# shield-iblock.net
KiCad netlist of a schematic drawn in EAGLE
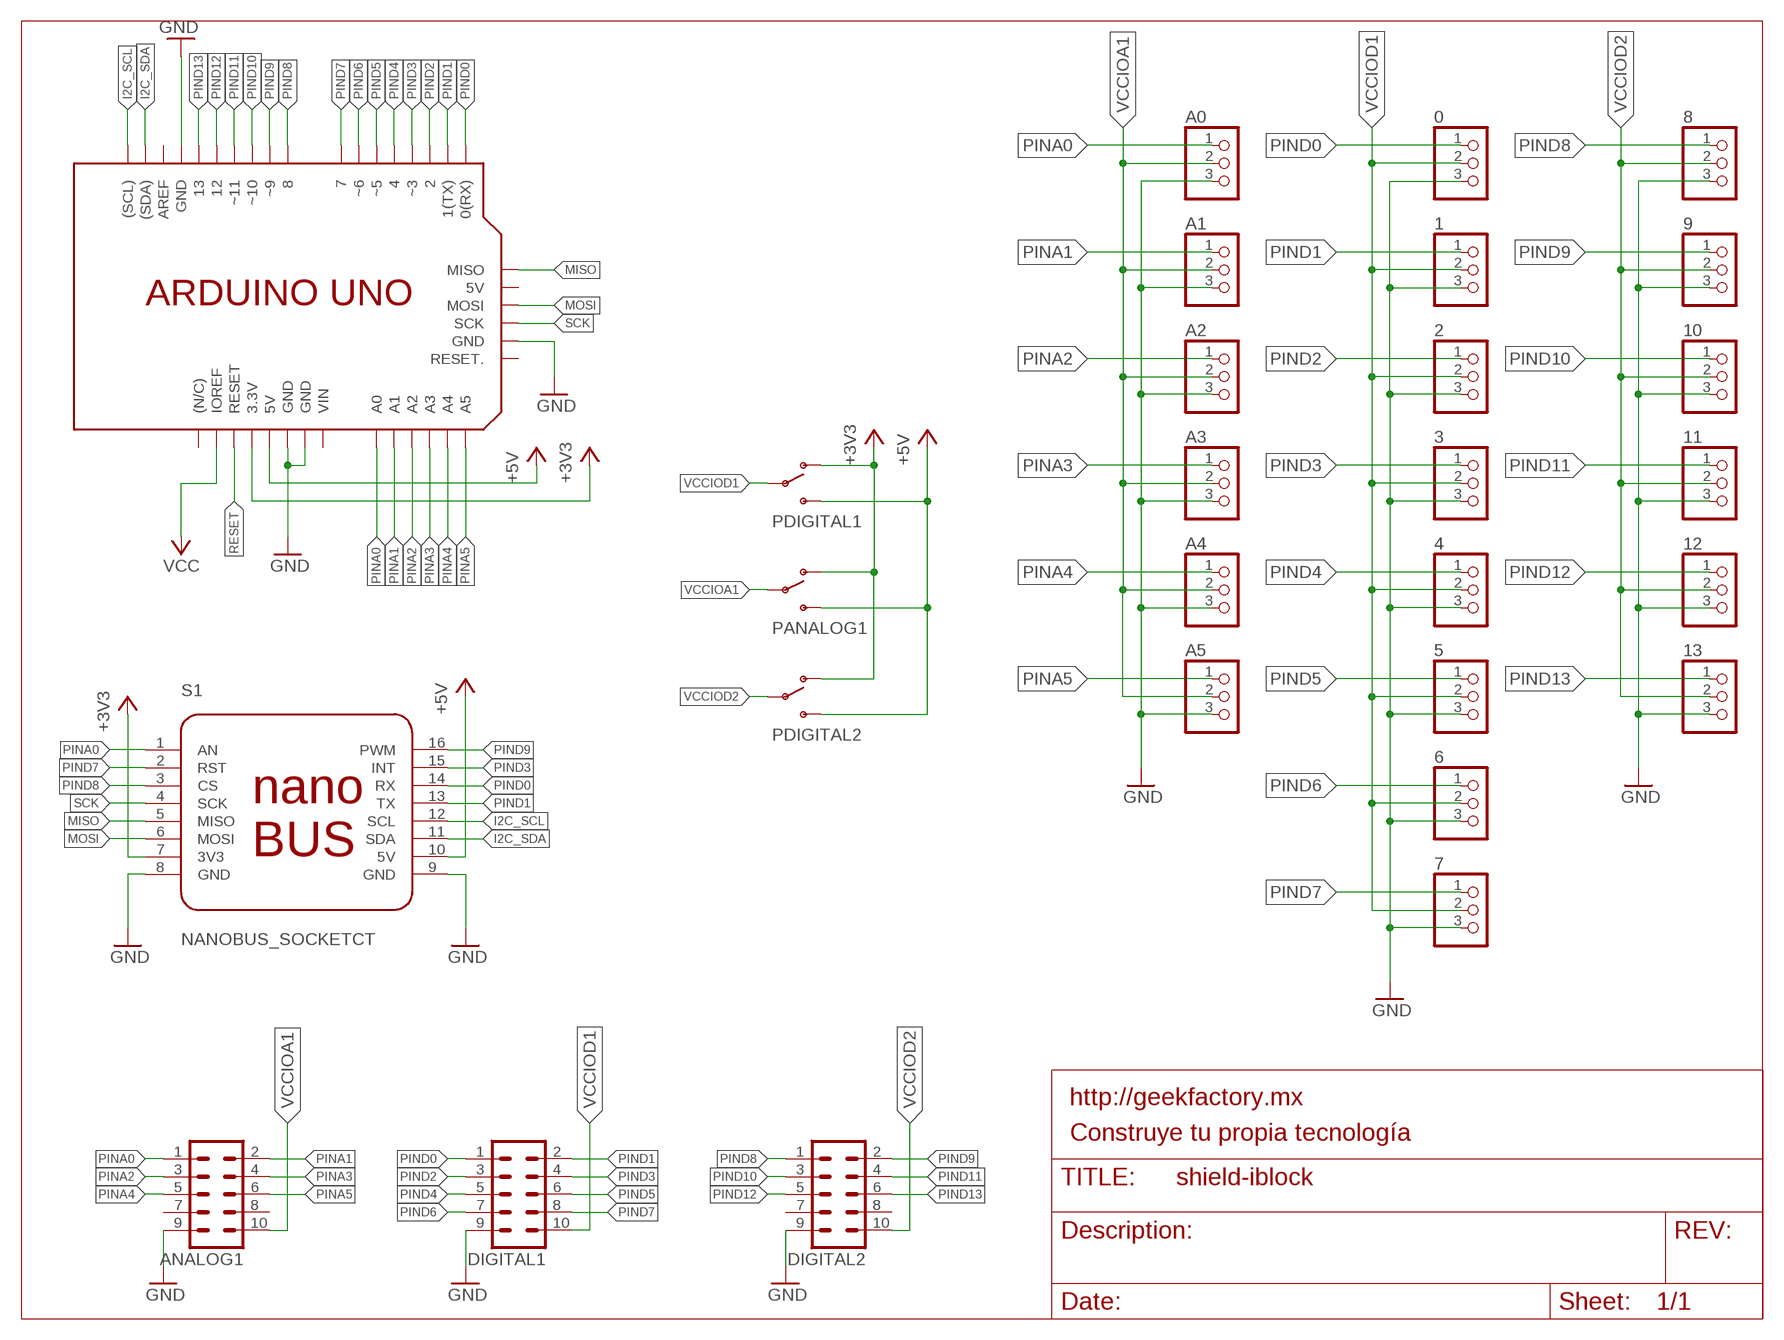
[diagram p0: schematic, sheet 1]

(export (version "E")
  (design (tool "Eeschema 10.0.6"))
  (components
    (comp (ref "0")
      (value "PINHD-1X3")
      (footprint "eagle-import:1X03")
      (libsource (lib "eagle-import") (part "PINHD-1X3"))
    )
    (comp (ref "1")
      (value "PINHD-1X3")
      (footprint "eagle-import:1X03")
      (libsource (lib "eagle-import") (part "PINHD-1X3"))
    )
    (comp (ref "2")
      (value "PINHD-1X3")
      (footprint "eagle-import:1X03")
      (libsource (lib "eagle-import") (part "PINHD-1X3"))
    )
    (comp (ref "3")
      (value "PINHD-1X3")
      (footprint "eagle-import:1X03")
      (libsource (lib "eagle-import") (part "PINHD-1X3"))
    )
    (comp (ref "4")
      (value "PINHD-1X3")
      (footprint "eagle-import:1X03")
      (libsource (lib "eagle-import") (part "PINHD-1X3"))
    )
    (comp (ref "5")
      (value "PINHD-1X3")
      (footprint "eagle-import:1X03")
      (libsource (lib "eagle-import") (part "PINHD-1X3"))
    )
    (comp (ref "6")
      (value "PINHD-1X3")
      (footprint "eagle-import:1X03")
      (libsource (lib "eagle-import") (part "PINHD-1X3"))
    )
    (comp (ref "7")
      (value "PINHD-1X3")
      (footprint "eagle-import:1X03")
      (libsource (lib "eagle-import") (part "PINHD-1X3"))
    )
    (comp (ref "8")
      (value "PINHD-1X3")
      (footprint "eagle-import:1X03")
      (libsource (lib "eagle-import") (part "PINHD-1X3"))
    )
    (comp (ref "9")
      (value "PINHD-1X3")
      (footprint "eagle-import:1X03")
      (libsource (lib "eagle-import") (part "PINHD-1X3"))
    )
    (comp (ref "10")
      (value "PINHD-1X3")
      (footprint "eagle-import:1X03")
      (libsource (lib "eagle-import") (part "PINHD-1X3"))
    )
    (comp (ref "11")
      (value "PINHD-1X3")
      (footprint "eagle-import:1X03")
      (libsource (lib "eagle-import") (part "PINHD-1X3"))
    )
    (comp (ref "12")
      (value "PINHD-1X3")
      (footprint "eagle-import:1X03")
      (libsource (lib "eagle-import") (part "PINHD-1X3"))
    )
    (comp (ref "13")
      (value "PINHD-1X3")
      (footprint "eagle-import:1X03")
      (libsource (lib "eagle-import") (part "PINHD-1X3"))
    )
    (comp (ref "A0")
      (value "PINHD-1X3")
      (footprint "eagle-import:1X03")
      (libsource (lib "eagle-import") (part "PINHD-1X3"))
    )
    (comp (ref "A1")
      (value "PINHD-1X3")
      (footprint "eagle-import:1X03")
      (libsource (lib "eagle-import") (part "PINHD-1X3"))
    )
    (comp (ref "A2")
      (value "PINHD-1X3")
      (footprint "eagle-import:1X03")
      (libsource (lib "eagle-import") (part "PINHD-1X3"))
    )
    (comp (ref "A3")
      (value "PINHD-1X3")
      (footprint "eagle-import:1X03")
      (libsource (lib "eagle-import") (part "PINHD-1X3"))
    )
    (comp (ref "A4")
      (value "PINHD-1X3")
      (footprint "eagle-import:1X03")
      (libsource (lib "eagle-import") (part "PINHD-1X3"))
    )
    (comp (ref "A5")
      (value "PINHD-1X3")
      (footprint "eagle-import:1X03")
      (libsource (lib "eagle-import") (part "PINHD-1X3"))
    )
    (comp (ref "ANALOG1")
      (value "MA05-2A")
      (footprint "eagle-import:MA05-2A")
      (libsource (lib "eagle-import") (part "MA05-2A"))
    )
    (comp (ref "ARDUINO1")
      (value "ARDUINO_UNO_NHNBR")
      (footprint "eagle-import:ARDUINO_UNO_NH_NB_ROUND")
      (libsource (lib "eagle-import") (part "ARDUINO_UNO_NHNBR"))
    )
    (comp (ref "DIGITAL1")
      (value "MA05-2A")
      (footprint "eagle-import:MA05-2A")
      (libsource (lib "eagle-import") (part "MA05-2A"))
    )
    (comp (ref "DIGITAL2")
      (value "MA05-2A")
      (footprint "eagle-import:MA05-2A")
      (libsource (lib "eagle-import") (part "MA05-2A"))
    )
    (comp (ref "PANALOG1")
      (value "SWITCH-SPSTPTH")
      (footprint "eagle-import:SWITCH-SPDT")
      (libsource (lib "eagle-import") (part "SWITCH-SPSTPTH"))
    )
    (comp (ref "PDIGITAL1")
      (value "SWITCH-SPSTPTH")
      (footprint "eagle-import:SWITCH-SPDT")
      (libsource (lib "eagle-import") (part "SWITCH-SPSTPTH"))
    )
    (comp (ref "PDIGITAL2")
      (value "SWITCH-SPSTPTH")
      (footprint "eagle-import:SWITCH-SPDT")
      (libsource (lib "eagle-import") (part "SWITCH-SPSTPTH"))
    )
    (comp (ref "S1")
      (value "NANOBUS_SOCKETCT")
      (footprint "eagle-import:NANOBUS_CONNECTOR_CLEAR_TOP")
      (libsource (lib "eagle-import") (part "NANOBUS_SOCKETCT"))
    )
  )
  (nets
    (net (code "1") (name "+3V3") (class "Default")
      (node (ref "ARDUINO1") (pin "3V3") (pinfunction "3.3V_3V3") (pintype "bidirectional"))
      (node (ref "PANALOG1") (pin "1") (pinfunction "O_1") (pintype "passive"))
      (node (ref "PDIGITAL1") (pin "1") (pinfunction "O_1") (pintype "passive"))
      (node (ref "PDIGITAL2") (pin "1") (pinfunction "O_1") (pintype "passive"))
      (node (ref "S1") (pin "7") (pinfunction "3V3_7") (pintype "power_in"))
    )
    (net (code "2") (name "+5V") (class "Default")
      (node (ref "ARDUINO1") (pin "5V") (pinfunction "5V_5V") (pintype "bidirectional"))
      (node (ref "PANALOG1") (pin "3") (pinfunction "S_3") (pintype "passive"))
      (node (ref "PDIGITAL1") (pin "3") (pinfunction "S_3") (pintype "passive"))
      (node (ref "PDIGITAL2") (pin "3") (pinfunction "S_3") (pintype "passive"))
      (node (ref "S1") (pin "10") (pinfunction "5V_10") (pintype "power_in"))
    )
    (net (code "3") (name "GND") (class "Default")
      (node (ref "0") (pin "3") (pinfunction "3_3") (pintype "passive"))
      (node (ref "1") (pin "3") (pinfunction "3_3") (pintype "passive"))
      (node (ref "10") (pin "3") (pinfunction "3_3") (pintype "passive"))
      (node (ref "11") (pin "3") (pinfunction "3_3") (pintype "passive"))
      (node (ref "12") (pin "3") (pinfunction "3_3") (pintype "passive"))
      (node (ref "13") (pin "3") (pinfunction "3_3") (pintype "passive"))
      (node (ref "2") (pin "3") (pinfunction "3_3") (pintype "passive"))
      (node (ref "3") (pin "3") (pinfunction "3_3") (pintype "passive"))
      (node (ref "4") (pin "3") (pinfunction "3_3") (pintype "passive"))
      (node (ref "5") (pin "3") (pinfunction "3_3") (pintype "passive"))
      (node (ref "6") (pin "3") (pinfunction "3_3") (pintype "passive"))
      (node (ref "7") (pin "3") (pinfunction "3_3") (pintype "passive"))
      (node (ref "8") (pin "3") (pinfunction "3_3") (pintype "passive"))
      (node (ref "9") (pin "3") (pinfunction "3_3") (pintype "passive"))
      (node (ref "A0") (pin "3") (pinfunction "3_3") (pintype "passive"))
      (node (ref "A1") (pin "3") (pinfunction "3_3") (pintype "passive"))
      (node (ref "A2") (pin "3") (pinfunction "3_3") (pintype "passive"))
      (node (ref "A3") (pin "3") (pinfunction "3_3") (pintype "passive"))
      (node (ref "A4") (pin "3") (pinfunction "3_3") (pintype "passive"))
      (node (ref "A5") (pin "3") (pinfunction "3_3") (pintype "passive"))
      (node (ref "ANALOG1") (pin "9") (pinfunction "9_9") (pintype "passive"))
      (node (ref "ARDUINO1") (pin "GND") (pinfunction "GND_GND") (pintype "bidirectional"))
      (node (ref "ARDUINO1") (pin "GND.") (pinfunction "GND_GND.") (pintype "bidirectional"))
      (node (ref "ARDUINO1") (pin "GND..") (pinfunction "GND_GND..") (pintype "bidirectional"))
      (node (ref "ARDUINO1") (pin "GND_") (pinfunction "GND_GND_") (pintype "bidirectional"))
      (node (ref "DIGITAL1") (pin "9") (pinfunction "9_9") (pintype "passive"))
      (node (ref "DIGITAL2") (pin "9") (pinfunction "9_9") (pintype "passive"))
      (node (ref "S1") (pin "8") (pinfunction "GND_8") (pintype "power_in"))
      (node (ref "S1") (pin "9") (pinfunction "GND_9") (pintype "power_in"))
    )
    (net (code "4") (name "I2C_SCL") (class "Default")
      (node (ref "ARDUINO1") (pin "SCL") (pinfunction "(SCL)_SCL") (pintype "bidirectional"))
      (node (ref "S1") (pin "12") (pinfunction "SCL_12") (pintype "passive"))
    )
    (net (code "5") (name "I2C_SDA") (class "Default")
      (node (ref "ARDUINO1") (pin "SDA") (pinfunction "(SDA)_SDA") (pintype "bidirectional"))
      (node (ref "S1") (pin "11") (pinfunction "SDA_11") (pintype "passive"))
    )
    (net (code "6") (name "MISO") (class "Default")
      (node (ref "ARDUINO1") (pin "MISO") (pinfunction "MISO_MISO") (pintype "bidirectional"))
      (node (ref "S1") (pin "5") (pinfunction "MISO_5") (pintype "passive"))
    )
    (net (code "7") (name "MOSI") (class "Default")
      (node (ref "ARDUINO1") (pin "MOSI") (pinfunction "MOSI_MOSI") (pintype "bidirectional"))
      (node (ref "S1") (pin "6") (pinfunction "MOSI_6") (pintype "passive"))
    )
    (net (code "8") (name "PINA0") (class "Default")
      (node (ref "A0") (pin "1") (pinfunction "1_1") (pintype "passive"))
      (node (ref "ANALOG1") (pin "1") (pinfunction "1_1") (pintype "passive"))
      (node (ref "ARDUINO1") (pin "A0") (pinfunction "A0_A0") (pintype "bidirectional"))
      (node (ref "S1") (pin "1") (pinfunction "AN_1") (pintype "passive"))
    )
    (net (code "9") (name "PINA1") (class "Default")
      (node (ref "A1") (pin "1") (pinfunction "1_1") (pintype "passive"))
      (node (ref "ANALOG1") (pin "2") (pinfunction "2_2") (pintype "passive"))
      (node (ref "ARDUINO1") (pin "A1") (pinfunction "A1_A1") (pintype "bidirectional"))
    )
    (net (code "10") (name "PINA2") (class "Default")
      (node (ref "A2") (pin "1") (pinfunction "1_1") (pintype "passive"))
      (node (ref "ANALOG1") (pin "3") (pinfunction "3_3") (pintype "passive"))
      (node (ref "ARDUINO1") (pin "A2") (pinfunction "A2_A2") (pintype "bidirectional"))
    )
    (net (code "11") (name "PINA3") (class "Default")
      (node (ref "A3") (pin "1") (pinfunction "1_1") (pintype "passive"))
      (node (ref "ANALOG1") (pin "4") (pinfunction "4_4") (pintype "passive"))
      (node (ref "ARDUINO1") (pin "A3") (pinfunction "A3_A3") (pintype "bidirectional"))
    )
    (net (code "12") (name "PINA4") (class "Default")
      (node (ref "A4") (pin "1") (pinfunction "1_1") (pintype "passive"))
      (node (ref "ANALOG1") (pin "5") (pinfunction "5_5") (pintype "passive"))
      (node (ref "ARDUINO1") (pin "A4") (pinfunction "A4_A4") (pintype "bidirectional"))
    )
    (net (code "13") (name "PINA5") (class "Default")
      (node (ref "A5") (pin "1") (pinfunction "1_1") (pintype "passive"))
      (node (ref "ANALOG1") (pin "6") (pinfunction "6_6") (pintype "passive"))
      (node (ref "ARDUINO1") (pin "A5") (pinfunction "A5_A5") (pintype "bidirectional"))
    )
    (net (code "14") (name "PIND0") (class "Default")
      (node (ref "0") (pin "1") (pinfunction "1_1") (pintype "passive"))
      (node (ref "ARDUINO1") (pin "0") (pinfunction "0(RX)_0") (pintype "bidirectional"))
      (node (ref "DIGITAL1") (pin "1") (pinfunction "1_1") (pintype "passive"))
      (node (ref "S1") (pin "14") (pinfunction "RX_14") (pintype "passive"))
    )
    (net (code "15") (name "PIND1") (class "Default")
      (node (ref "1") (pin "1") (pinfunction "1_1") (pintype "passive"))
      (node (ref "ARDUINO1") (pin "1") (pinfunction "1(TX)_1") (pintype "bidirectional"))
      (node (ref "DIGITAL1") (pin "2") (pinfunction "2_2") (pintype "passive"))
      (node (ref "S1") (pin "13") (pinfunction "TX_13") (pintype "passive"))
    )
    (net (code "16") (name "PIND2") (class "Default")
      (node (ref "2") (pin "1") (pinfunction "1_1") (pintype "passive"))
      (node (ref "ARDUINO1") (pin "2") (pinfunction "2_2") (pintype "bidirectional"))
      (node (ref "DIGITAL1") (pin "3") (pinfunction "3_3") (pintype "passive"))
    )
    (net (code "17") (name "PIND3") (class "Default")
      (node (ref "3") (pin "1") (pinfunction "1_1") (pintype "passive"))
      (node (ref "ARDUINO1") (pin "3") (pinfunction "~{3}_3") (pintype "bidirectional"))
      (node (ref "DIGITAL1") (pin "4") (pinfunction "4_4") (pintype "passive"))
      (node (ref "S1") (pin "15") (pinfunction "INT_15") (pintype "passive"))
    )
    (net (code "18") (name "PIND4") (class "Default")
      (node (ref "4") (pin "1") (pinfunction "1_1") (pintype "passive"))
      (node (ref "ARDUINO1") (pin "4") (pinfunction "4_4") (pintype "bidirectional"))
      (node (ref "DIGITAL1") (pin "5") (pinfunction "5_5") (pintype "passive"))
    )
    (net (code "19") (name "PIND5") (class "Default")
      (node (ref "5") (pin "1") (pinfunction "1_1") (pintype "passive"))
      (node (ref "ARDUINO1") (pin "5") (pinfunction "~{5}_5") (pintype "bidirectional"))
      (node (ref "DIGITAL1") (pin "6") (pinfunction "6_6") (pintype "passive"))
    )
    (net (code "20") (name "PIND6") (class "Default")
      (node (ref "6") (pin "1") (pinfunction "1_1") (pintype "passive"))
      (node (ref "ARDUINO1") (pin "6") (pinfunction "~{6}_6") (pintype "bidirectional"))
      (node (ref "DIGITAL1") (pin "7") (pinfunction "7_7") (pintype "passive"))
    )
    (net (code "21") (name "PIND7") (class "Default")
      (node (ref "7") (pin "1") (pinfunction "1_1") (pintype "passive"))
      (node (ref "ARDUINO1") (pin "7") (pinfunction "7_7") (pintype "bidirectional"))
      (node (ref "DIGITAL1") (pin "8") (pinfunction "8_8") (pintype "passive"))
      (node (ref "S1") (pin "2") (pinfunction "RST_2") (pintype "passive"))
    )
    (net (code "22") (name "PIND8") (class "Default")
      (node (ref "8") (pin "1") (pinfunction "1_1") (pintype "passive"))
      (node (ref "ARDUINO1") (pin "8") (pinfunction "8_8") (pintype "bidirectional"))
      (node (ref "DIGITAL2") (pin "1") (pinfunction "1_1") (pintype "passive"))
      (node (ref "S1") (pin "3") (pinfunction "CS_3") (pintype "passive"))
    )
    (net (code "23") (name "PIND9") (class "Default")
      (node (ref "9") (pin "1") (pinfunction "1_1") (pintype "passive"))
      (node (ref "ARDUINO1") (pin "9") (pinfunction "~{9}_9") (pintype "bidirectional"))
      (node (ref "DIGITAL2") (pin "2") (pinfunction "2_2") (pintype "passive"))
      (node (ref "S1") (pin "16") (pinfunction "PWM_16") (pintype "passive"))
    )
    (net (code "24") (name "PIND10") (class "Default")
      (node (ref "10") (pin "1") (pinfunction "1_1") (pintype "passive"))
      (node (ref "ARDUINO1") (pin "10") (pinfunction "~{10}_10") (pintype "bidirectional"))
      (node (ref "DIGITAL2") (pin "3") (pinfunction "3_3") (pintype "passive"))
    )
    (net (code "25") (name "PIND11") (class "Default")
      (node (ref "11") (pin "1") (pinfunction "1_1") (pintype "passive"))
      (node (ref "ARDUINO1") (pin "11") (pinfunction "~{11}_11") (pintype "bidirectional"))
      (node (ref "DIGITAL2") (pin "4") (pinfunction "4_4") (pintype "passive"))
    )
    (net (code "26") (name "PIND12") (class "Default")
      (node (ref "12") (pin "1") (pinfunction "1_1") (pintype "passive"))
      (node (ref "ARDUINO1") (pin "12") (pinfunction "12_12") (pintype "bidirectional"))
      (node (ref "DIGITAL2") (pin "5") (pinfunction "5_5") (pintype "passive"))
    )
    (net (code "27") (name "PIND13") (class "Default")
      (node (ref "13") (pin "1") (pinfunction "1_1") (pintype "passive"))
      (node (ref "ARDUINO1") (pin "13") (pinfunction "13_13") (pintype "bidirectional"))
      (node (ref "DIGITAL2") (pin "6") (pinfunction "6_6") (pintype "passive"))
    )
    (net (code "28") (name "RESET") (class "Default")
      (node (ref "ARDUINO1") (pin "RST") (pinfunction "RESET_RST") (pintype "bidirectional"))
    )
    (net (code "29") (name "SCK") (class "Default")
      (node (ref "ARDUINO1") (pin "SCK") (pinfunction "SCK_SCK") (pintype "bidirectional"))
      (node (ref "S1") (pin "4") (pinfunction "SCK_4") (pintype "passive"))
    )
    (net (code "30") (name "VCC") (class "Default")
      (node (ref "ARDUINO1") (pin "IOR") (pinfunction "IOREF_IOR") (pintype "bidirectional"))
    )
    (net (code "31") (name "VCCIOA1") (class "Default")
      (node (ref "A0") (pin "2") (pinfunction "2_2") (pintype "passive"))
      (node (ref "A1") (pin "2") (pinfunction "2_2") (pintype "passive"))
      (node (ref "A2") (pin "2") (pinfunction "2_2") (pintype "passive"))
      (node (ref "A3") (pin "2") (pinfunction "2_2") (pintype "passive"))
      (node (ref "A4") (pin "2") (pinfunction "2_2") (pintype "passive"))
      (node (ref "A5") (pin "2") (pinfunction "2_2") (pintype "passive"))
      (node (ref "ANALOG1") (pin "10") (pinfunction "10_10") (pintype "passive"))
      (node (ref "PANALOG1") (pin "2") (pinfunction "P_2") (pintype "passive"))
    )
    (net (code "32") (name "VCCIOD1") (class "Default")
      (node (ref "0") (pin "2") (pinfunction "2_2") (pintype "passive"))
      (node (ref "1") (pin "2") (pinfunction "2_2") (pintype "passive"))
      (node (ref "2") (pin "2") (pinfunction "2_2") (pintype "passive"))
      (node (ref "3") (pin "2") (pinfunction "2_2") (pintype "passive"))
      (node (ref "4") (pin "2") (pinfunction "2_2") (pintype "passive"))
      (node (ref "5") (pin "2") (pinfunction "2_2") (pintype "passive"))
      (node (ref "6") (pin "2") (pinfunction "2_2") (pintype "passive"))
      (node (ref "7") (pin "2") (pinfunction "2_2") (pintype "passive"))
      (node (ref "DIGITAL1") (pin "10") (pinfunction "10_10") (pintype "passive"))
      (node (ref "PDIGITAL1") (pin "2") (pinfunction "P_2") (pintype "passive"))
    )
    (net (code "33") (name "VCCIOD2") (class "Default")
      (node (ref "10") (pin "2") (pinfunction "2_2") (pintype "passive"))
      (node (ref "11") (pin "2") (pinfunction "2_2") (pintype "passive"))
      (node (ref "12") (pin "2") (pinfunction "2_2") (pintype "passive"))
      (node (ref "13") (pin "2") (pinfunction "2_2") (pintype "passive"))
      (node (ref "8") (pin "2") (pinfunction "2_2") (pintype "passive"))
      (node (ref "9") (pin "2") (pinfunction "2_2") (pintype "passive"))
      (node (ref "DIGITAL2") (pin "10") (pinfunction "10_10") (pintype "passive"))
      (node (ref "PDIGITAL2") (pin "2") (pinfunction "P_2") (pintype "passive"))
    )
    (net (code "34") (name "unconnected-(ANALOG1-Pad7)") (class "Default")
      (node (ref "ANALOG1") (pin "7") (pinfunction "7_7") (pintype "passive"))
    )
    (net (code "35") (name "unconnected-(ANALOG1-Pad8)") (class "Default")
      (node (ref "ANALOG1") (pin "8") (pinfunction "8_8") (pintype "passive"))
    )
    (net (code "36") (name "unconnected-(ARDUINO1-(N{slash}C)-PadNC)") (class "Default")
      (node (ref "ARDUINO1") (pin "NC") (pinfunction "(N/C)_NC") (pintype "bidirectional"))
    )
    (net (code "37") (name "unconnected-(ARDUINO1-5V-Pad+5V)") (class "Default")
      (node (ref "ARDUINO1") (pin "+5V") (pinfunction "5V_+5V") (pintype "bidirectional"))
    )
    (net (code "38") (name "unconnected-(ARDUINO1-PadAREF)") (class "Default")
      (node (ref "ARDUINO1") (pin "AREF") (pinfunction "AREF_AREF") (pintype "bidirectional"))
    )
    (net (code "39") (name "unconnected-(ARDUINO1-PadRESET.)") (class "Default")
      (node (ref "ARDUINO1") (pin "RESET.") (pinfunction "RESET._RESET.") (pintype "bidirectional"))
    )
    (net (code "40") (name "unconnected-(ARDUINO1-PadVIN)") (class "Default")
      (node (ref "ARDUINO1") (pin "VIN") (pinfunction "VIN_VIN") (pintype "bidirectional"))
    )
    (net (code "41") (name "unconnected-(DIGITAL2-Pad7)") (class "Default")
      (node (ref "DIGITAL2") (pin "7") (pinfunction "7_7") (pintype "passive"))
    )
    (net (code "42") (name "unconnected-(DIGITAL2-Pad8)") (class "Default")
      (node (ref "DIGITAL2") (pin "8") (pinfunction "8_8") (pintype "passive"))
    )
  )
)
